# WorkshySwitch.net
KiCad netlist of a schematic drawn in EAGLE
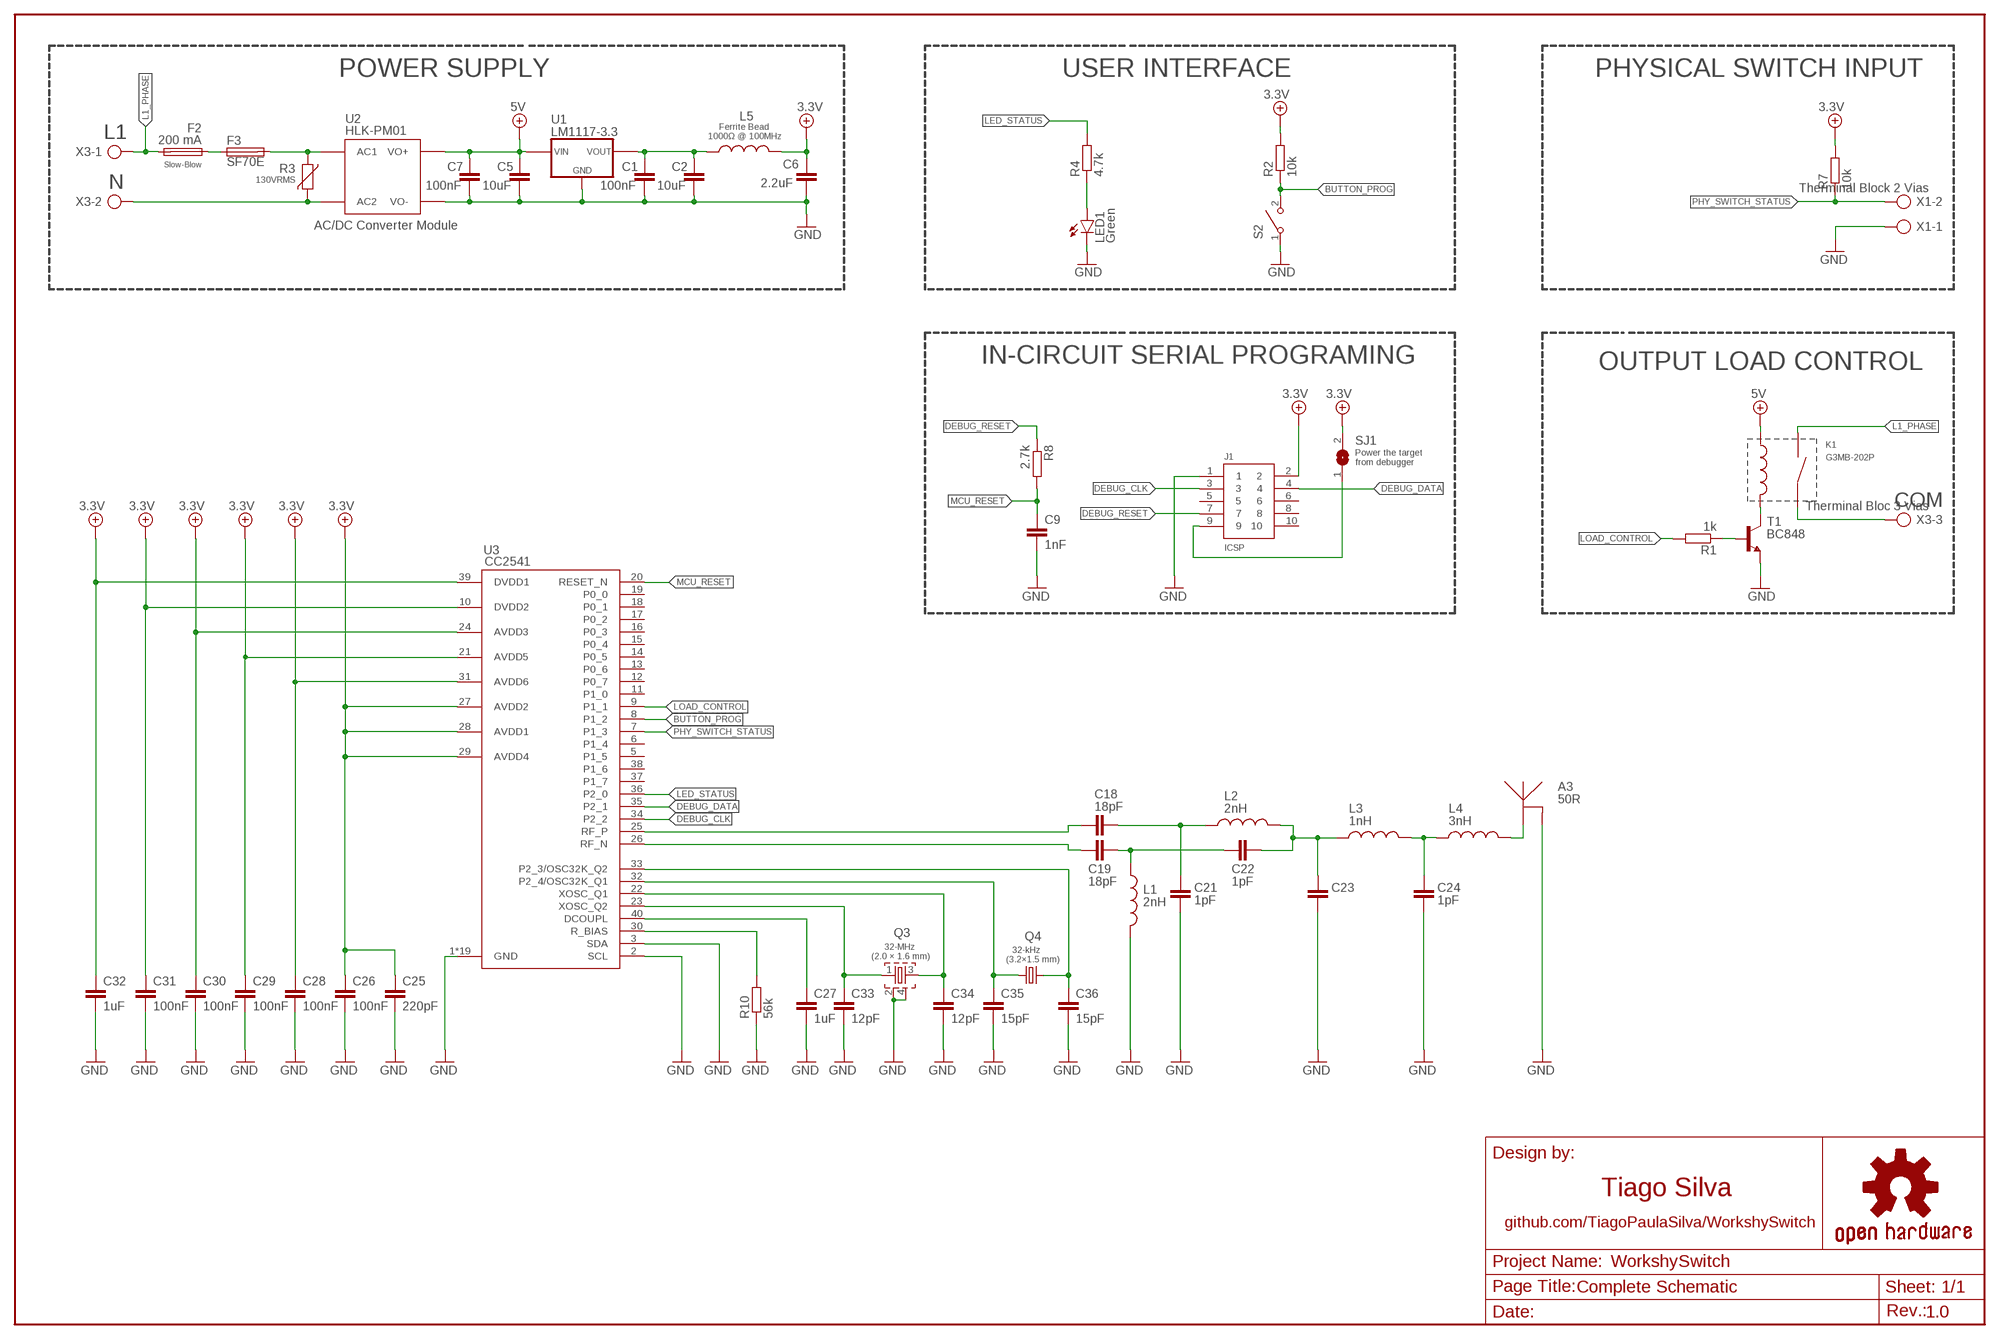
[diagram p0: schematic, sheet 1]

(export (version "E")
  (design (tool "Eeschema 10.0.6"))
  (components
    (comp (ref "A3")
      (value "50R")
      (footprint "eagle-import:MIFA")
      (libsource (lib "eagle-import") (part "ANTENNA"))
    )
    (comp (ref "C1")
      (value "100nF")
      (footprint "eagle-import:C0603")
      (libsource (lib "eagle-import") (part "C-EUC0603"))
    )
    (comp (ref "C2")
      (value "10uF")
      (footprint "eagle-import:C0603")
      (libsource (lib "eagle-import") (part "C-EUC0603"))
    )
    (comp (ref "C5")
      (value "10uF")
      (footprint "eagle-import:C0603")
      (libsource (lib "eagle-import") (part "C-EUC0603"))
    )
    (comp (ref "C6")
      (value "2.2uF")
      (footprint "eagle-import:C0402")
      (libsource (lib "eagle-import") (part "C0402"))
    )
    (comp (ref "C7")
      (value "100nF")
      (footprint "eagle-import:C0603")
      (libsource (lib "eagle-import") (part "C-EUC0603"))
    )
    (comp (ref "C9")
      (value "1nF")
      (footprint "eagle-import:C0402")
      (libsource (lib "eagle-import") (part "C0402"))
    )
    (comp (ref "C18")
      (value "18pF")
      (footprint "eagle-import:C0402")
      (libsource (lib "eagle-import") (part "C0402"))
    )
    (comp (ref "C19")
      (value "18pF")
      (footprint "eagle-import:C0402")
      (libsource (lib "eagle-import") (part "C0402"))
    )
    (comp (ref "C21")
      (value "1pF")
      (footprint "eagle-import:C0402")
      (libsource (lib "eagle-import") (part "C0402"))
    )
    (comp (ref "C22")
      (value "1pF")
      (footprint "eagle-import:C0402")
      (libsource (lib "eagle-import") (part "C0402"))
    )
    (comp (ref "C23")
      (value "C0402")
      (footprint "eagle-import:C0402")
      (libsource (lib "eagle-import") (part "C0402"))
    )
    (comp (ref "C24")
      (value "1pF")
      (footprint "eagle-import:C0402")
      (libsource (lib "eagle-import") (part "C0402"))
    )
    (comp (ref "C25")
      (value "220pF")
      (footprint "eagle-import:C0402")
      (libsource (lib "eagle-import") (part "C0402"))
    )
    (comp (ref "C26")
      (value "100nF")
      (footprint "eagle-import:C0402")
      (libsource (lib "eagle-import") (part "C0402"))
    )
    (comp (ref "C27")
      (value "1uF")
      (footprint "eagle-import:C0402")
      (libsource (lib "eagle-import") (part "C0402"))
    )
    (comp (ref "C28")
      (value "100nF")
      (footprint "eagle-import:C0402")
      (libsource (lib "eagle-import") (part "C0402"))
    )
    (comp (ref "C29")
      (value "100nF")
      (footprint "eagle-import:C0402")
      (libsource (lib "eagle-import") (part "C0402"))
    )
    (comp (ref "C30")
      (value "100nF")
      (footprint "eagle-import:C0402")
      (libsource (lib "eagle-import") (part "C0402"))
    )
    (comp (ref "C31")
      (value "100nF")
      (footprint "eagle-import:C0402")
      (libsource (lib "eagle-import") (part "C0402"))
    )
    (comp (ref "C32")
      (value "1uF")
      (footprint "eagle-import:C0402")
      (libsource (lib "eagle-import") (part "C0402"))
    )
    (comp (ref "C33")
      (value "12pF")
      (footprint "eagle-import:C0402")
      (libsource (lib "eagle-import") (part "C0402"))
    )
    (comp (ref "C34")
      (value "12pF")
      (footprint "eagle-import:C0402")
      (libsource (lib "eagle-import") (part "C0402"))
    )
    (comp (ref "C35")
      (value "15pF")
      (footprint "eagle-import:C0402")
      (libsource (lib "eagle-import") (part "C0402"))
    )
    (comp (ref "C36")
      (value "15pF")
      (footprint "eagle-import:C0402")
      (libsource (lib "eagle-import") (part "C0402"))
    )
    (comp (ref "F2")
      (value "200 mA")
      (footprint "eagle-import:QPL")
      (libsource (lib "eagle-import") (part "QPL"))
    )
    (comp (ref "F3")
      (value "SF70E")
      (footprint "eagle-import:LITTLEFUSE")
      (libsource (lib "eagle-import") (part "LITTLEFUSE"))
    )
    (comp (ref "J1")
      (value "ICSP")
      (footprint "eagle-import:SHF-105-01-X-D-SM")
      (fields (field (name "MF") "Samtec") (field (name "MP") "SHF-105-01-F-D-SM"))
      (libsource (lib "eagle-import") (part "SHF-105-01-X-D-SM"))
    )
    (comp (ref "K1")
      (value "G3MB-202P")
      (footprint "eagle-import:RELAY_G3MB202PDC12")
      (fields (field (name "MF") "Omron Automation") (field (name "MP") "G3MB-202P-DC12"))
      (libsource (lib "eagle-import") (part "G3MB202PDC12"))
    )
    (comp (ref "L1")
      (value "2nH")
      (footprint "eagle-import:C0402")
      (libsource (lib "eagle-import") (part "L0402"))
    )
    (comp (ref "L2")
      (value "2nH")
      (footprint "eagle-import:C0402")
      (libsource (lib "eagle-import") (part "L0402"))
    )
    (comp (ref "L3")
      (value "1nH")
      (footprint "eagle-import:C0402")
      (libsource (lib "eagle-import") (part "L0402"))
    )
    (comp (ref "L4")
      (value "3nH")
      (footprint "eagle-import:C0402")
      (libsource (lib "eagle-import") (part "L0402"))
    )
    (comp (ref "L5")
      (value "Ferrite Bead")
      (footprint "eagle-import:C0402")
      (libsource (lib "eagle-import") (part "L0402"))
    )
    (comp (ref "LED1")
      (value "Green")
      (footprint "eagle-import:CHIP-LED0805")
      (libsource (lib "eagle-import") (part "LEDCHIP-LED0805"))
    )
    (comp (ref "Q3")
      (value "32-MHz")
      (footprint "eagle-import:FA-128")
      (libsource (lib "eagle-import") (part "FA-128"))
    )
    (comp (ref "Q4")
      (value "32-kHz")
      (footprint "eagle-import:3.2X1.5")
      (libsource (lib "eagle-import") (part "KX-327-NHF"))
    )
    (comp (ref "R1")
      (value "1k")
      (footprint "eagle-import:C0402")
      (libsource (lib "eagle-import") (part "R0402"))
    )
    (comp (ref "R2")
      (value "10k")
      (footprint "eagle-import:C0402")
      (libsource (lib "eagle-import") (part "R0402"))
    )
    (comp (ref "R3")
      (value "130VRMS")
      (footprint "eagle-import:S05K11")
      (libsource (lib "eagle-import") (part "VARISTORS05K11"))
    )
    (comp (ref "R4")
      (value "4.7k")
      (footprint "eagle-import:C0402")
      (libsource (lib "eagle-import") (part "R0402"))
    )
    (comp (ref "R7")
      (value "10k")
      (footprint "eagle-import:C0402")
      (libsource (lib "eagle-import") (part "R0402"))
    )
    (comp (ref "R8")
      (value "2.7k")
      (footprint "eagle-import:C0402")
      (libsource (lib "eagle-import") (part "R0402"))
    )
    (comp (ref "R10")
      (value "56k")
      (footprint "eagle-import:C0402")
      (libsource (lib "eagle-import") (part "R0402"))
    )
    (comp (ref "S2")
      (value "434121050816")
      (footprint "eagle-import:434121050816")
      (fields (field (name "MF") "Wurth Electronics"))
      (libsource (lib "eagle-import") (part "434121050816"))
    )
    (comp (ref "SJ1")
      (value "Jumper")
      (footprint "eagle-import:SJ")
      (libsource (lib "eagle-import") (part "SJ"))
    )
    (comp (ref "T1")
      (value "BC848")
      (footprint "eagle-import:SOT23")
      (libsource (lib "eagle-import") (part "BC848"))
    )
    (comp (ref "U1")
      (value "LM1117-3.3")
      (footprint "eagle-import:SOT223")
      (fields (field (name "MF") "Texas Instruments") (field (name "MP") "REG1117"))
      (libsource (lib "eagle-import") (part "REG1117"))
    )
    (comp (ref "U2")
      (value "HLK-PM01")
      (footprint "eagle-import:HLK-PM01")
      (fields (field (name "MF") "Hi-link") (field (name "MP") "hlk-pm01"))
      (libsource (lib "eagle-import") (part "HLK-PM01"))
    )
    (comp (ref "U3")
      (value "CC2541")
      (footprint "eagle-import:QFN50P600X600X100-41N")
      (fields (field (name "MF") "Texas Instruments") (field (name "MP") "CC2541F256RHAT"))
      (libsource (lib "eagle-import") (part "CC2541F256RHAT"))
    )
    (comp (ref "X1")
      (value "Therminal Block 2 Vias")
      (footprint "eagle-import:AK500_2")
      (libsource (lib "eagle-import") (part "AK500/2"))
    )
    (comp (ref "X3")
      (value "Therminal Bloc 3 Vias")
      (footprint "eagle-import:AK500_3")
      (libsource (lib "eagle-import") (part "AK500/3"))
    )
  )
  (nets
    (net (code "1") (name "3.3V") (class "Default")
      (node (ref "C25") (pin "1") (pinfunction "1_1") (pintype "passive"))
      (node (ref "C26") (pin "1") (pinfunction "1_1") (pintype "passive"))
      (node (ref "C28") (pin "1") (pinfunction "1_1") (pintype "passive"))
      (node (ref "C29") (pin "1") (pinfunction "1_1") (pintype "passive"))
      (node (ref "C30") (pin "1") (pinfunction "1_1") (pintype "passive"))
      (node (ref "C31") (pin "1") (pinfunction "1_1") (pintype "passive"))
      (node (ref "C32") (pin "1") (pinfunction "1_1") (pintype "passive"))
      (node (ref "C6") (pin "1") (pinfunction "1_1") (pintype "passive"))
      (node (ref "J1") (pin "2") (pinfunction "2_2") (pintype "bidirectional"))
      (node (ref "L5") (pin "1") (pinfunction "1_1") (pintype "passive"))
      (node (ref "R2") (pin "2") (pinfunction "2_2") (pintype "passive"))
      (node (ref "R7") (pin "2") (pinfunction "2_2") (pintype "passive"))
      (node (ref "SJ1") (pin "2") (pinfunction "2_2") (pintype "passive"))
      (node (ref "U3") (pin "10") (pinfunction "DVDD2_10") (pintype "power_in"))
      (node (ref "U3") (pin "21") (pinfunction "AVDD5_21") (pintype "power_in"))
      (node (ref "U3") (pin "24") (pinfunction "AVDD3_24") (pintype "power_in"))
      (node (ref "U3") (pin "27") (pinfunction "AVDD2_27") (pintype "power_in"))
      (node (ref "U3") (pin "28") (pinfunction "AVDD1_28") (pintype "power_in"))
      (node (ref "U3") (pin "29") (pinfunction "AVDD4_29") (pintype "power_in"))
      (node (ref "U3") (pin "31") (pinfunction "AVDD6_31") (pintype "power_in"))
      (node (ref "U3") (pin "39") (pinfunction "DVDD1_39") (pintype "power_in"))
    )
    (net (code "2") (name "5V") (class "Default")
      (node (ref "C5") (pin "1") (pinfunction "1_1") (pintype "passive"))
      (node (ref "C7") (pin "1") (pinfunction "1_1") (pintype "passive"))
      (node (ref "K1") (pin "3") (pinfunction "+_3") (pintype "power_in"))
      (node (ref "U1") (pin "3") (pinfunction "VIN_3") (pintype "input"))
      (node (ref "U2") (pin "P$4") (pinfunction "VO+_P$4") (pintype "power_in"))
    )
    (net (code "3") (name "BUTTON_PROG") (class "Default")
      (node (ref "R2") (pin "1") (pinfunction "1_1") (pintype "passive"))
      (node (ref "S2") (pin "2") (pinfunction "2_2") (pintype "passive"))
      (node (ref "U3") (pin "8") (pinfunction "P1_2_8") (pintype "bidirectional"))
    )
    (net (code "4") (name "DEBUG_CLK") (class "Default")
      (node (ref "J1") (pin "3") (pinfunction "3_3") (pintype "bidirectional"))
      (node (ref "U3") (pin "34") (pinfunction "P2_2_34") (pintype "bidirectional"))
    )
    (net (code "5") (name "DEBUG_DATA") (class "Default")
      (node (ref "J1") (pin "4") (pinfunction "4_4") (pintype "bidirectional"))
      (node (ref "U3") (pin "35") (pinfunction "P2_1_35") (pintype "bidirectional"))
    )
    (net (code "6") (name "DEBUG_RESET") (class "Default")
      (node (ref "J1") (pin "7") (pinfunction "7_7") (pintype "bidirectional"))
      (node (ref "R8") (pin "1") (pinfunction "1_1") (pintype "passive"))
    )
    (net (code "7") (name "GND") (class "Default")
      (node (ref "A3") (pin "GND") (pinfunction "GND_GND") (pintype "power_in"))
      (node (ref "C1") (pin "2") (pinfunction "2_2") (pintype "passive"))
      (node (ref "C2") (pin "2") (pinfunction "2_2") (pintype "passive"))
      (node (ref "C21") (pin "2") (pinfunction "2_2") (pintype "passive"))
      (node (ref "C23") (pin "1") (pinfunction "1_1") (pintype "passive"))
      (node (ref "C24") (pin "2") (pinfunction "2_2") (pintype "passive"))
      (node (ref "C25") (pin "2") (pinfunction "2_2") (pintype "passive"))
      (node (ref "C26") (pin "2") (pinfunction "2_2") (pintype "passive"))
      (node (ref "C27") (pin "2") (pinfunction "2_2") (pintype "passive"))
      (node (ref "C28") (pin "2") (pinfunction "2_2") (pintype "passive"))
      (node (ref "C29") (pin "2") (pinfunction "2_2") (pintype "passive"))
      (node (ref "C30") (pin "2") (pinfunction "2_2") (pintype "passive"))
      (node (ref "C31") (pin "2") (pinfunction "2_2") (pintype "passive"))
      (node (ref "C32") (pin "2") (pinfunction "2_2") (pintype "passive"))
      (node (ref "C33") (pin "2") (pinfunction "2_2") (pintype "passive"))
      (node (ref "C34") (pin "2") (pinfunction "2_2") (pintype "passive"))
      (node (ref "C35") (pin "2") (pinfunction "2_2") (pintype "passive"))
      (node (ref "C36") (pin "2") (pinfunction "2_2") (pintype "passive"))
      (node (ref "C5") (pin "2") (pinfunction "2_2") (pintype "passive"))
      (node (ref "C6") (pin "2") (pinfunction "2_2") (pintype "passive"))
      (node (ref "C7") (pin "2") (pinfunction "2_2") (pintype "passive"))
      (node (ref "C9") (pin "2") (pinfunction "2_2") (pintype "passive"))
      (node (ref "J1") (pin "1") (pinfunction "1_1") (pintype "bidirectional"))
      (node (ref "L1") (pin "2") (pinfunction "2_2") (pintype "passive"))
      (node (ref "LED1") (pin "C") (pinfunction "C_C") (pintype "passive"))
      (node (ref "Q3") (pin "2") (pinfunction "2_2") (pintype "passive"))
      (node (ref "Q3") (pin "4") (pinfunction "4_4") (pintype "passive"))
      (node (ref "R10") (pin "1") (pinfunction "1_1") (pintype "passive"))
      (node (ref "S2") (pin "1") (pinfunction "1_1") (pintype "passive"))
      (node (ref "T1") (pin "2") (pinfunction "E_2") (pintype "passive"))
      (node (ref "U1") (pin "1") (pinfunction "GND_1") (pintype "power_in"))
      (node (ref "U2") (pin "P$3") (pinfunction "VO-_P$3") (pintype "power_in"))
      (node (ref "U3") (pin "1") (pinfunction "GND_1") (pintype "power_in"))
      (node (ref "U3") (pin "2") (pinfunction "SCL_2") (pintype "bidirectional"))
      (node (ref "U3") (pin "3") (pinfunction "SDA_3") (pintype "bidirectional"))
      (node (ref "U3") (pin "4") (pinfunction "GND_4") (pintype "power_in"))
      (node (ref "U3") (pin "41") (pinfunction "GND_41") (pintype "power_in"))
      (node (ref "U3") (pin "42") (pinfunction "GND_42") (pintype "power_in"))
      (node (ref "U3") (pin "43") (pinfunction "GND_43") (pintype "power_in"))
      (node (ref "U3") (pin "44") (pinfunction "GND_44") (pintype "power_in"))
      (node (ref "U3") (pin "45") (pinfunction "GND_45") (pintype "power_in"))
      (node (ref "U3") (pin "46") (pinfunction "GND_46") (pintype "power_in"))
      (node (ref "U3") (pin "47") (pinfunction "GND_47") (pintype "power_in"))
      (node (ref "U3") (pin "48") (pinfunction "GND_48") (pintype "power_in"))
      (node (ref "U3") (pin "49") (pinfunction "GND_49") (pintype "power_in"))
      (node (ref "U3") (pin "50") (pinfunction "GND_50") (pintype "power_in"))
      (node (ref "U3") (pin "51") (pinfunction "GND_51") (pintype "power_in"))
      (node (ref "U3") (pin "52") (pinfunction "GND_52") (pintype "power_in"))
      (node (ref "U3") (pin "53") (pinfunction "GND_53") (pintype "power_in"))
      (node (ref "U3") (pin "54") (pinfunction "GND_54") (pintype "power_in"))
      (node (ref "U3") (pin "55") (pinfunction "GND_55") (pintype "power_in"))
      (node (ref "U3") (pin "56") (pinfunction "GND_56") (pintype "power_in"))
      (node (ref "U3") (pin "57") (pinfunction "GND_57") (pintype "power_in"))
      (node (ref "X1") (pin "1") (pinfunction "KL_1") (pintype "passive"))
    )
    (net (code "8") (name "L1_PHASE") (class "Default")
      (node (ref "F2") (pin "2") (pinfunction "2_2") (pintype "passive"))
      (node (ref "K1") (pin "1") (pinfunction "L1_1") (pintype "power_in"))
      (node (ref "X3") (pin "1") (pinfunction "KL_1") (pintype "passive"))
    )
    (net (code "9") (name "LED_STATUS") (class "Default")
      (node (ref "R4") (pin "2") (pinfunction "2_2") (pintype "passive"))
      (node (ref "U3") (pin "36") (pinfunction "P2_0_36") (pintype "bidirectional"))
    )
    (net (code "10") (name "LOAD_CONTROL") (class "Default")
      (node (ref "R1") (pin "2") (pinfunction "2_2") (pintype "passive"))
      (node (ref "U3") (pin "9") (pinfunction "P1_1_9") (pintype "bidirectional"))
    )
    (net (code "11") (name "MCU_RESET") (class "Default")
      (node (ref "C9") (pin "1") (pinfunction "1_1") (pintype "passive"))
      (node (ref "R8") (pin "2") (pinfunction "2_2") (pintype "passive"))
      (node (ref "U3") (pin "20") (pinfunction "RESET_N_20") (pintype "input"))
    )
    (net (code "12") (name "Net-(A3-PadFEED)") (class "Default")
      (node (ref "A3") (pin "FEED") (pinfunction "FEED_FEED") (pintype "bidirectional"))
      (node (ref "L4") (pin "2") (pinfunction "2_2") (pintype "passive"))
    )
    (net (code "13") (name "Net-(C1-Pad1)") (class "Default")
      (node (ref "C1") (pin "1") (pinfunction "1_1") (pintype "passive"))
      (node (ref "C2") (pin "1") (pinfunction "1_1") (pintype "passive"))
      (node (ref "L5") (pin "2") (pinfunction "2_2") (pintype "passive"))
      (node (ref "U1") (pin "2") (pinfunction "VOUT_2") (pintype "output"))
      (node (ref "U1") (pin "4") (pinfunction "VOUT_4") (pintype "output"))
    )
    (net (code "14") (name "Net-(C18-Pad2)") (class "Default")
      (node (ref "C18") (pin "2") (pinfunction "2_2") (pintype "passive"))
      (node (ref "C21") (pin "1") (pinfunction "1_1") (pintype "passive"))
      (node (ref "L2") (pin "1") (pinfunction "1_1") (pintype "passive"))
    )
    (net (code "15") (name "Net-(C19-Pad1)") (class "Default")
      (node (ref "C19") (pin "1") (pinfunction "1_1") (pintype "passive"))
      (node (ref "C22") (pin "2") (pinfunction "2_2") (pintype "passive"))
      (node (ref "L1") (pin "1") (pinfunction "1_1") (pintype "passive"))
    )
    (net (code "16") (name "Net-(C22-Pad1)") (class "Default")
      (node (ref "C22") (pin "1") (pinfunction "1_1") (pintype "passive"))
      (node (ref "C23") (pin "2") (pinfunction "2_2") (pintype "passive"))
      (node (ref "L2") (pin "2") (pinfunction "2_2") (pintype "passive"))
      (node (ref "L3") (pin "1") (pinfunction "1_1") (pintype "passive"))
    )
    (net (code "17") (name "Net-(C24-Pad1)") (class "Default")
      (node (ref "C24") (pin "1") (pinfunction "1_1") (pintype "passive"))
      (node (ref "L3") (pin "2") (pinfunction "2_2") (pintype "passive"))
      (node (ref "L4") (pin "1") (pinfunction "1_1") (pintype "passive"))
    )
    (net (code "18") (name "Net-(F2-Pad1)") (class "Default")
      (node (ref "F2") (pin "1") (pinfunction "1_1") (pintype "passive"))
      (node (ref "F3") (pin "1") (pinfunction "1_1") (pintype "passive"))
    )
    (net (code "19") (name "Net-(J1-Pad9)") (class "Default")
      (node (ref "J1") (pin "9") (pinfunction "9_9") (pintype "bidirectional"))
      (node (ref "SJ1") (pin "1") (pinfunction "1_1") (pintype "passive"))
    )
    (net (code "20") (name "Net-(K1--)") (class "Default")
      (node (ref "K1") (pin "4") (pinfunction "-_4") (pintype "power_in"))
      (node (ref "T1") (pin "3") (pinfunction "C_3") (pintype "passive"))
    )
    (net (code "21") (name "Net-(K1-L2)") (class "Default")
      (node (ref "K1") (pin "2") (pinfunction "L2_2") (pintype "power_in"))
      (node (ref "X3") (pin "3") (pinfunction "KL_3") (pintype "passive"))
    )
    (net (code "22") (name "Net-(LED1-PadA)") (class "Default")
      (node (ref "LED1") (pin "A") (pinfunction "A_A") (pintype "passive"))
      (node (ref "R4") (pin "1") (pinfunction "1_1") (pintype "passive"))
    )
    (net (code "23") (name "Net-(T1-B)") (class "Default")
      (node (ref "R1") (pin "1") (pinfunction "1_1") (pintype "passive"))
      (node (ref "T1") (pin "1") (pinfunction "B_1") (pintype "passive"))
    )
    (net (code "24") (name "Net-(U2-AC1)") (class "Default")
      (node (ref "F3") (pin "2") (pinfunction "2_2") (pintype "passive"))
      (node (ref "R3") (pin "1") (pinfunction "1_1") (pintype "passive"))
      (node (ref "U2") (pin "P$1") (pinfunction "AC1_P$1") (pintype "input"))
    )
    (net (code "25") (name "Net-(U2-AC2)") (class "Default")
      (node (ref "R3") (pin "2") (pinfunction "2_2") (pintype "passive"))
      (node (ref "U2") (pin "P$2") (pinfunction "AC2_P$2") (pintype "input"))
      (node (ref "X3") (pin "2") (pinfunction "KL_2") (pintype "passive"))
    )
    (net (code "26") (name "Net-(U3-DCOUPL)") (class "Default")
      (node (ref "C27") (pin "1") (pinfunction "1_1") (pintype "passive"))
      (node (ref "U3") (pin "40") (pinfunction "DCOUPL_40") (pintype "bidirectional"))
    )
    (net (code "27") (name "Net-(U3-P2_3{slash}OSC32K_Q2)") (class "Default")
      (node (ref "C36") (pin "1") (pinfunction "1_1") (pintype "passive"))
      (node (ref "Q4") (pin "2") (pinfunction "2_2") (pintype "passive"))
      (node (ref "U3") (pin "33") (pinfunction "P2_3/OSC32K_Q2_33") (pintype "bidirectional"))
    )
    (net (code "28") (name "Net-(U3-P2_4{slash}OSC32K_Q1)") (class "Default")
      (node (ref "C35") (pin "1") (pinfunction "1_1") (pintype "passive"))
      (node (ref "Q4") (pin "1") (pinfunction "1_1") (pintype "passive"))
      (node (ref "U3") (pin "32") (pinfunction "P2_4/OSC32K_Q1_32") (pintype "bidirectional"))
    )
    (net (code "29") (name "Net-(U3-RF_N)") (class "Default")
      (node (ref "C19") (pin "2") (pinfunction "2_2") (pintype "passive"))
      (node (ref "U3") (pin "26") (pinfunction "RF_N_26") (pintype "bidirectional"))
    )
    (net (code "30") (name "Net-(U3-RF_P)") (class "Default")
      (node (ref "C18") (pin "1") (pinfunction "1_1") (pintype "passive"))
      (node (ref "U3") (pin "25") (pinfunction "RF_P_25") (pintype "bidirectional"))
    )
    (net (code "31") (name "Net-(U3-R_BIAS)") (class "Default")
      (node (ref "R10") (pin "2") (pinfunction "2_2") (pintype "passive"))
      (node (ref "U3") (pin "30") (pinfunction "R_BIAS_30") (pintype "bidirectional"))
    )
    (net (code "32") (name "Net-(U3-XOSC_Q1)") (class "Default")
      (node (ref "C34") (pin "1") (pinfunction "1_1") (pintype "passive"))
      (node (ref "Q3") (pin "3") (pinfunction "3_3") (pintype "passive"))
      (node (ref "U3") (pin "22") (pinfunction "XOSC_Q1_22") (pintype "bidirectional"))
    )
    (net (code "33") (name "Net-(U3-XOSC_Q2)") (class "Default")
      (node (ref "C33") (pin "1") (pinfunction "1_1") (pintype "passive"))
      (node (ref "Q3") (pin "1") (pinfunction "1_1") (pintype "passive"))
      (node (ref "U3") (pin "23") (pinfunction "XOSC_Q2_23") (pintype "bidirectional"))
    )
    (net (code "34") (name "PHY_SWITCH_STATUS") (class "Default")
      (node (ref "R7") (pin "1") (pinfunction "1_1") (pintype "passive"))
      (node (ref "U3") (pin "7") (pinfunction "P1_3_7") (pintype "bidirectional"))
      (node (ref "X1") (pin "2") (pinfunction "KL_2") (pintype "passive"))
    )
    (net (code "35") (name "unconnected-(J1-Pad5)") (class "Default")
      (node (ref "J1") (pin "5") (pinfunction "5_5") (pintype "bidirectional"))
    )
    (net (code "36") (name "unconnected-(J1-Pad6)") (class "Default")
      (node (ref "J1") (pin "6") (pinfunction "6_6") (pintype "bidirectional"))
    )
    (net (code "37") (name "unconnected-(J1-Pad8)") (class "Default")
      (node (ref "J1") (pin "8") (pinfunction "8_8") (pintype "bidirectional"))
    )
    (net (code "38") (name "unconnected-(J1-Pad10)") (class "Default")
      (node (ref "J1") (pin "10") (pinfunction "10_10") (pintype "bidirectional"))
    )
    (net (code "39") (name "unconnected-(U3-P0_0-Pad19)") (class "Default")
      (node (ref "U3") (pin "19") (pinfunction "P0_0_19") (pintype "bidirectional"))
    )
    (net (code "40") (name "unconnected-(U3-P0_1-Pad18)") (class "Default")
      (node (ref "U3") (pin "18") (pinfunction "P0_1_18") (pintype "bidirectional"))
    )
    (net (code "41") (name "unconnected-(U3-P0_2-Pad17)") (class "Default")
      (node (ref "U3") (pin "17") (pinfunction "P0_2_17") (pintype "bidirectional"))
    )
    (net (code "42") (name "unconnected-(U3-P0_3-Pad16)") (class "Default")
      (node (ref "U3") (pin "16") (pinfunction "P0_3_16") (pintype "bidirectional"))
    )
    (net (code "43") (name "unconnected-(U3-P0_4-Pad15)") (class "Default")
      (node (ref "U3") (pin "15") (pinfunction "P0_4_15") (pintype "bidirectional"))
    )
    (net (code "44") (name "unconnected-(U3-P0_5-Pad14)") (class "Default")
      (node (ref "U3") (pin "14") (pinfunction "P0_5_14") (pintype "bidirectional"))
    )
    (net (code "45") (name "unconnected-(U3-P0_6-Pad13)") (class "Default")
      (node (ref "U3") (pin "13") (pinfunction "P0_6_13") (pintype "bidirectional"))
    )
    (net (code "46") (name "unconnected-(U3-P0_7-Pad12)") (class "Default")
      (node (ref "U3") (pin "12") (pinfunction "P0_7_12") (pintype "bidirectional"))
    )
    (net (code "47") (name "unconnected-(U3-P1_0-Pad11)") (class "Default")
      (node (ref "U3") (pin "11") (pinfunction "P1_0_11") (pintype "bidirectional"))
    )
    (net (code "48") (name "unconnected-(U3-P1_4-Pad6)") (class "Default")
      (node (ref "U3") (pin "6") (pinfunction "P1_4_6") (pintype "bidirectional"))
    )
    (net (code "49") (name "unconnected-(U3-P1_5-Pad5)") (class "Default")
      (node (ref "U3") (pin "5") (pinfunction "P1_5_5") (pintype "bidirectional"))
    )
    (net (code "50") (name "unconnected-(U3-P1_6-Pad38)") (class "Default")
      (node (ref "U3") (pin "38") (pinfunction "P1_6_38") (pintype "bidirectional"))
    )
    (net (code "51") (name "unconnected-(U3-P1_7-Pad37)") (class "Default")
      (node (ref "U3") (pin "37") (pinfunction "P1_7_37") (pintype "bidirectional"))
    )
  )
)
